# Regulators.net
KiCad netlist of a schematic drawn in Altium Designer
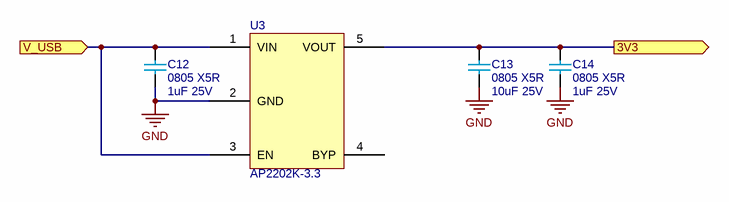
[diagram p0: Regulators.SchDoc]

(export (version "E")
  (design (tool "Eeschema 10.0.6"))
  (components
    (comp (ref "C12")
      (value "0805 X5R")
      (footprint "0805 - TALL")
      (description "0805, X5R or better")
      (fields (field (name "ALTIUM_VALUE") "1uF 25V"))
      (libsource (lib "Chip_Passives") (part "Cap 1uF 25V"))
    )
    (comp (ref "C13")
      (value "0805 X5R")
      (footprint "0805 - TALL")
      (description "0805, X5R or better")
      (fields (field (name "ALTIUM_VALUE") "10uF 25V"))
      (libsource (lib "Chip_Passives") (part "Cap 10uF 25V"))
    )
    (comp (ref "C14")
      (value "0805 X5R")
      (footprint "0805 - TALL")
      (description "0805, X5R or better")
      (fields (field (name "ALTIUM_VALUE") "1uF 25V"))
      (libsource (lib "Chip_Passives") (part "Cap 1uF 25V"))
    )
    (comp (ref "U3")
      (value "AP2202K-3.3")
      (footprint "AP2202 - SOT95P270X145-5N")
      (description "3.3V 150mA LDO regulator")
      (libsource (lib "PowerSupply") (part "AP2202K-3.3"))
    )
  )
  (nets
    (net (code "1") (name "/3V3") (class "Default")
      (node (ref "C13") (pin "2") (pinfunction "2_2") (pintype "passive"))
      (node (ref "C14") (pin "2") (pinfunction "2_2") (pintype "passive"))
      (node (ref "U3") (pin "5") (pinfunction "VOUT_5") (pintype "passive"))
    )
    (net (code "2") (name "/V_USB") (class "Default")
      (node (ref "C12") (pin "2") (pinfunction "2_2") (pintype "passive"))
      (node (ref "U3") (pin "1") (pinfunction "VIN_1") (pintype "passive"))
      (node (ref "U3") (pin "3") (pinfunction "EN_3") (pintype "passive"))
    )
    (net (code "3") (name "GND") (class "Default")
      (node (ref "C12") (pin "1") (pinfunction "1_1") (pintype "passive"))
      (node (ref "C13") (pin "1") (pinfunction "1_1") (pintype "passive"))
      (node (ref "C14") (pin "1") (pinfunction "1_1") (pintype "passive"))
      (node (ref "U3") (pin "2") (pinfunction "GND_2") (pintype "passive"))
    )
    (net (code "4") (name "unconnected-(U3-BYP-Pad4)") (class "Default")
      (node (ref "U3") (pin "4") (pinfunction "BYP_4") (pintype "passive"))
    )
  )
)
